# 48x_49x_Breakout_Board.net
KiCad netlist of a schematic drawn in EAGLE
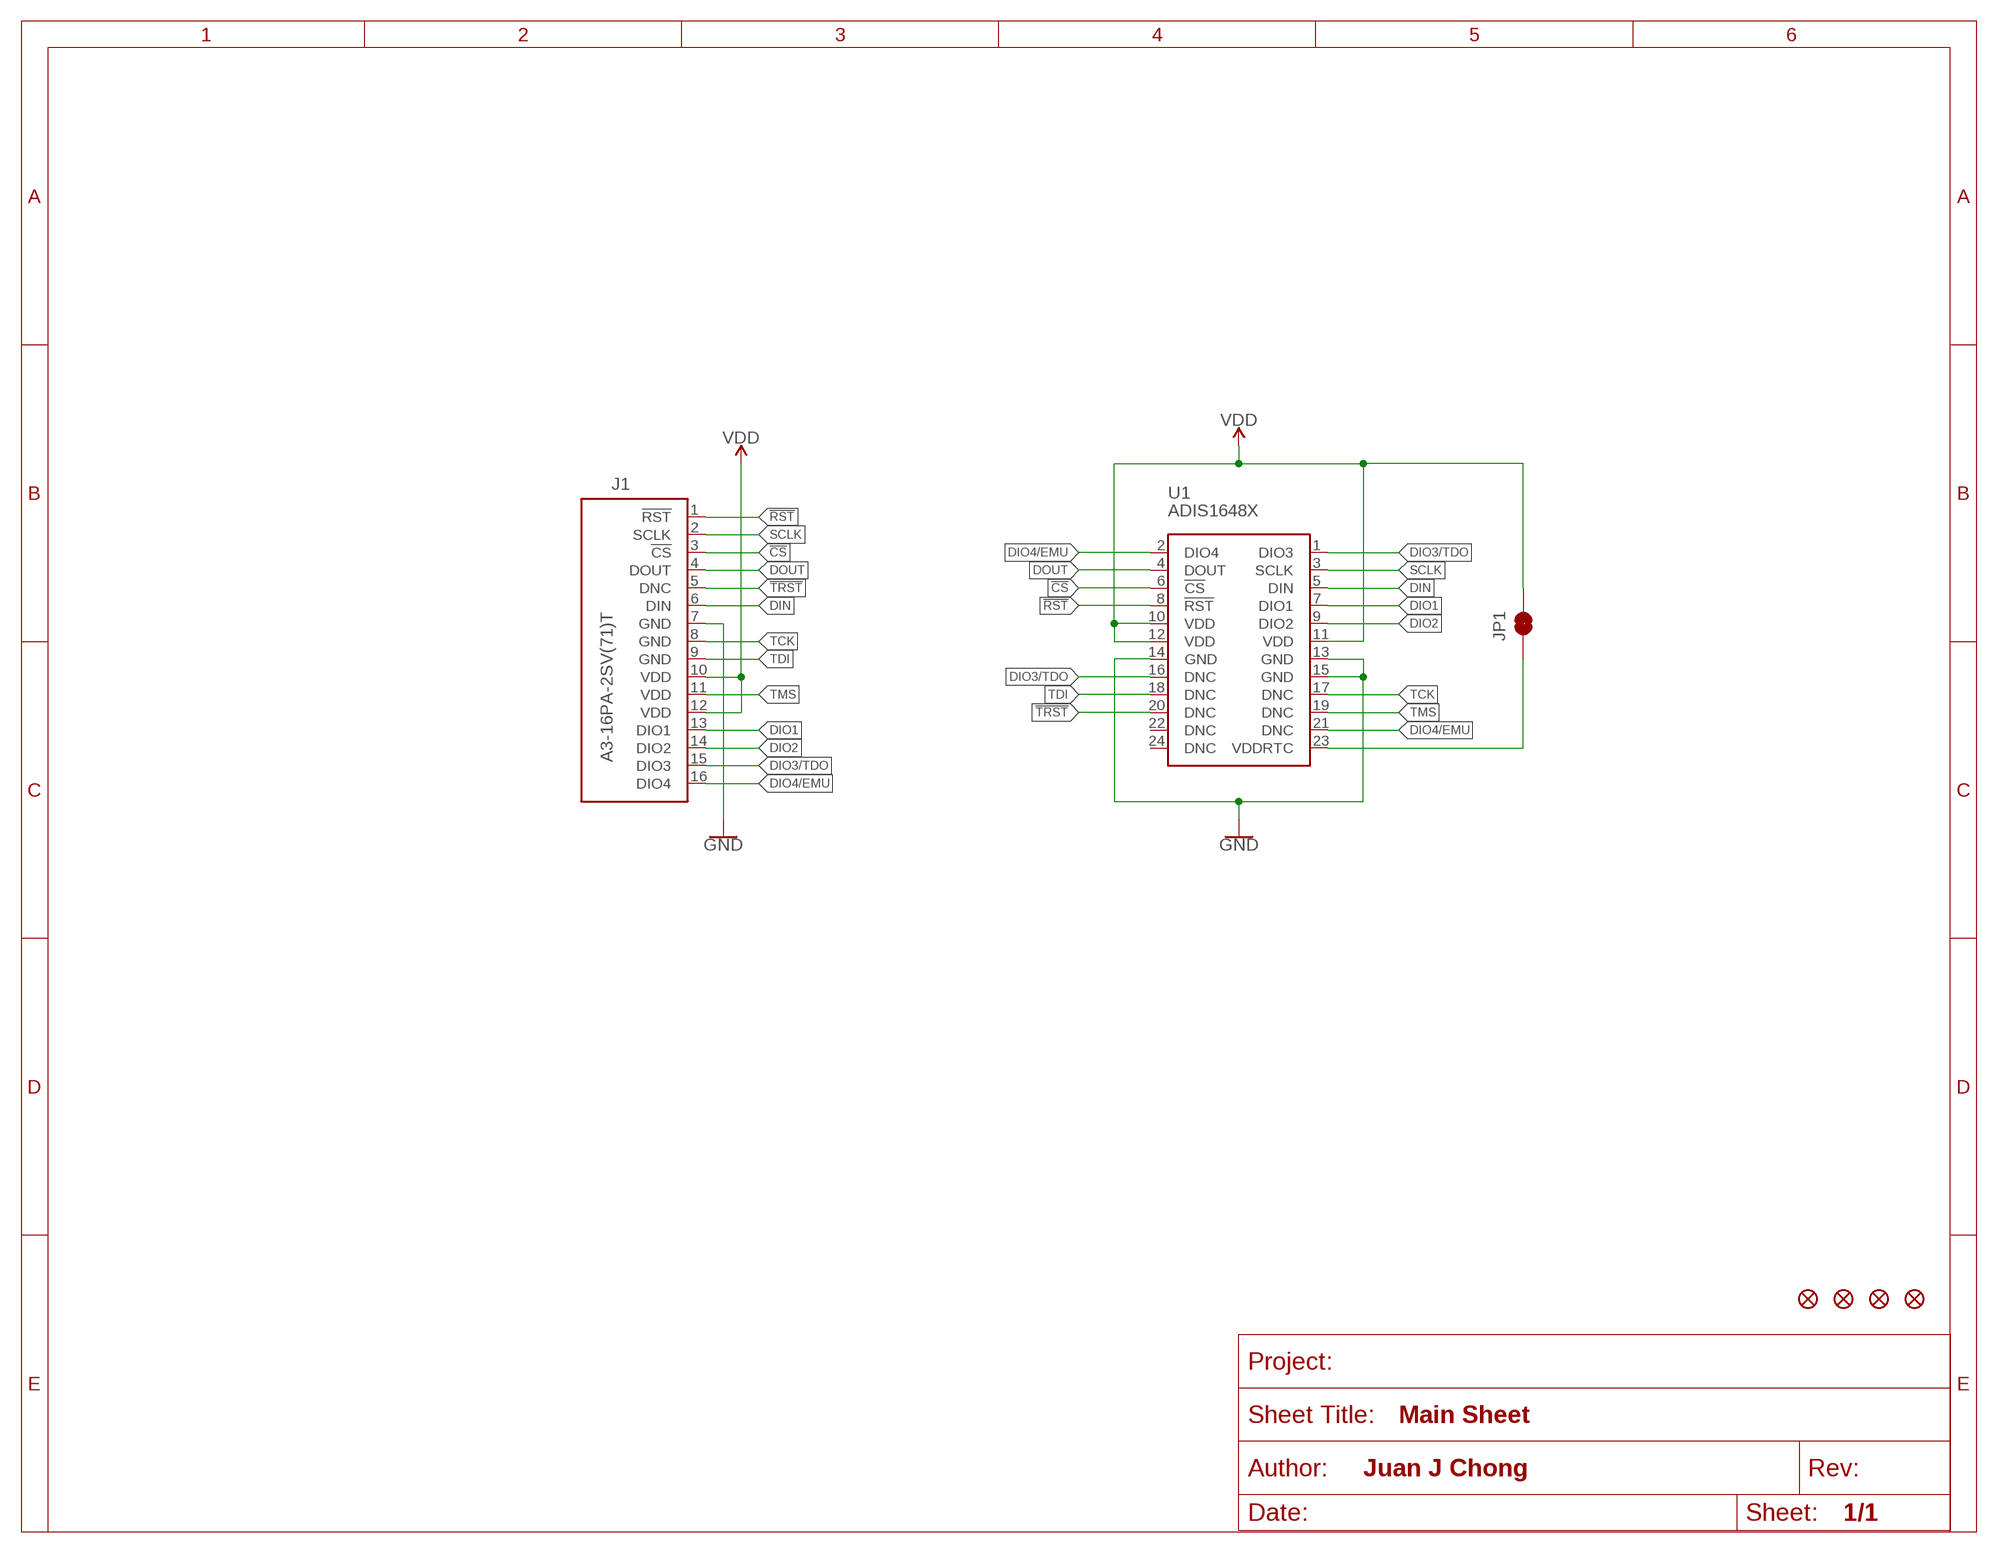
[diagram p0: schematic, sheet 1]

(export (version "E")
  (design (tool "Eeschema 10.0.6"))
  (components
    (comp (ref "FD1")
      (value "FIDUCIAL1X2")
      (footprint "eagle-import:FIDUCIAL-1X2")
      (libsource (lib "eagle-import") (part "FIDUCIAL1X2"))
    )
    (comp (ref "FD2")
      (value "FIDUCIAL1X2")
      (footprint "eagle-import:FIDUCIAL-1X2")
      (libsource (lib "eagle-import") (part "FIDUCIAL1X2"))
    )
    (comp (ref "FD3")
      (value "FIDUCIAL1X2")
      (footprint "eagle-import:FIDUCIAL-1X2")
      (libsource (lib "eagle-import") (part "FIDUCIAL1X2"))
    )
    (comp (ref "FD4")
      (value "FIDUCIAL1X2")
      (footprint "eagle-import:FIDUCIAL-1X2")
      (libsource (lib "eagle-import") (part "FIDUCIAL1X2"))
    )
    (comp (ref "J1")
      (value "A3-16PA-2SV(71)T")
      (footprint "eagle-import:A3-16PA-2SV(71)-TOP")
      (libsource (lib "eagle-import") (part "A3-16PA-2SV(71)T"))
    )
    (comp (ref "JP1")
      (value "JUMPER-SMT_2_NC_TRACE_SILK")
      (footprint "eagle-import:SMT-JUMPER_2_NC_TRACE_SILK")
      (libsource (lib "eagle-import") (part "JUMPER-SMT_2_NC_TRACE_SILK"))
    )
    (comp (ref "U1")
      (value "ADIS1648X")
      (footprint "eagle-import:ADIS1648X")
      (libsource (lib "eagle-import") (part "ADIS1648X"))
    )
  )
  (nets
    (net (code "1") (name "/~{CS}") (class "Default")
      (node (ref "J1") (pin "3") (pinfunction "~{CS}_3") (pintype "bidirectional"))
      (node (ref "U1") (pin "6") (pinfunction "~{CS}_6") (pintype "bidirectional"))
    )
    (net (code "2") (name "/~{RST}") (class "Default")
      (node (ref "J1") (pin "1") (pinfunction "~{RST}_1") (pintype "bidirectional"))
      (node (ref "U1") (pin "8") (pinfunction "~{RST}_8") (pintype "bidirectional"))
    )
    (net (code "3") (name "/~{TRST}") (class "Default")
      (node (ref "J1") (pin "5") (pinfunction "DNC_5") (pintype "bidirectional"))
      (node (ref "U1") (pin "20") (pinfunction "DNC_20") (pintype "bidirectional"))
    )
    (net (code "4") (name "DIN") (class "Default")
      (node (ref "J1") (pin "6") (pinfunction "DIN_6") (pintype "bidirectional"))
      (node (ref "U1") (pin "5") (pinfunction "DIN_5") (pintype "bidirectional"))
    )
    (net (code "5") (name "DIO1") (class "Default")
      (node (ref "J1") (pin "13") (pinfunction "DIO1_13") (pintype "bidirectional"))
      (node (ref "U1") (pin "7") (pinfunction "DIO1_7") (pintype "bidirectional"))
    )
    (net (code "6") (name "DIO2") (class "Default")
      (node (ref "J1") (pin "14") (pinfunction "DIO2_14") (pintype "bidirectional"))
      (node (ref "U1") (pin "9") (pinfunction "DIO2_9") (pintype "bidirectional"))
    )
    (net (code "7") (name "DIO3{slash}TDO") (class "Default")
      (node (ref "J1") (pin "15") (pinfunction "DIO3_15") (pintype "bidirectional"))
      (node (ref "U1") (pin "1") (pinfunction "DIO3_1") (pintype "bidirectional"))
      (node (ref "U1") (pin "16") (pinfunction "DNC_16") (pintype "bidirectional"))
    )
    (net (code "8") (name "DIO4{slash}EMU") (class "Default")
      (node (ref "J1") (pin "16") (pinfunction "DIO4_16") (pintype "bidirectional"))
      (node (ref "U1") (pin "2") (pinfunction "DIO4_2") (pintype "bidirectional"))
      (node (ref "U1") (pin "21") (pinfunction "DNC_21") (pintype "bidirectional"))
    )
    (net (code "9") (name "DOUT") (class "Default")
      (node (ref "J1") (pin "4") (pinfunction "DOUT_4") (pintype "bidirectional"))
      (node (ref "U1") (pin "4") (pinfunction "DOUT_4") (pintype "bidirectional"))
    )
    (net (code "10") (name "GND") (class "Default")
      (node (ref "J1") (pin "7") (pinfunction "GND_7") (pintype "bidirectional"))
      (node (ref "U1") (pin "13") (pinfunction "GND_13") (pintype "bidirectional"))
      (node (ref "U1") (pin "14") (pinfunction "GND_14") (pintype "bidirectional"))
      (node (ref "U1") (pin "15") (pinfunction "GND_15") (pintype "bidirectional"))
    )
    (net (code "11") (name "Net-(U1-VDDRTC)") (class "Default")
      (node (ref "JP1") (pin "1") (pinfunction "1_1") (pintype "passive"))
      (node (ref "U1") (pin "23") (pinfunction "VDDRTC_23") (pintype "bidirectional"))
    )
    (net (code "12") (name "SCLK") (class "Default")
      (node (ref "J1") (pin "2") (pinfunction "SCLK_2") (pintype "bidirectional"))
      (node (ref "U1") (pin "3") (pinfunction "SCLK_3") (pintype "bidirectional"))
    )
    (net (code "13") (name "TCK") (class "Default")
      (node (ref "J1") (pin "8") (pinfunction "GND_8") (pintype "bidirectional"))
      (node (ref "U1") (pin "17") (pinfunction "DNC_17") (pintype "bidirectional"))
    )
    (net (code "14") (name "TDI") (class "Default")
      (node (ref "J1") (pin "9") (pinfunction "GND_9") (pintype "bidirectional"))
      (node (ref "U1") (pin "18") (pinfunction "DNC_18") (pintype "bidirectional"))
    )
    (net (code "15") (name "TMS") (class "Default")
      (node (ref "J1") (pin "11") (pinfunction "VDD_11") (pintype "bidirectional"))
      (node (ref "U1") (pin "19") (pinfunction "DNC_19") (pintype "bidirectional"))
    )
    (net (code "16") (name "VDD") (class "Default")
      (node (ref "J1") (pin "10") (pinfunction "VDD_10") (pintype "bidirectional"))
      (node (ref "J1") (pin "12") (pinfunction "VDD_12") (pintype "bidirectional"))
      (node (ref "JP1") (pin "2") (pinfunction "2_2") (pintype "passive"))
      (node (ref "U1") (pin "10") (pinfunction "VDD_10") (pintype "bidirectional"))
      (node (ref "U1") (pin "11") (pinfunction "VDD_11") (pintype "bidirectional"))
      (node (ref "U1") (pin "12") (pinfunction "VDD_12") (pintype "bidirectional"))
    )
    (net (code "17") (name "unconnected-(U1-DNC-Pad22)") (class "Default")
      (node (ref "U1") (pin "22") (pinfunction "DNC_22") (pintype "bidirectional"))
    )
    (net (code "18") (name "unconnected-(U1-DNC-Pad24)") (class "Default")
      (node (ref "U1") (pin "24") (pinfunction "DNC_24") (pintype "bidirectional"))
    )
  )
)
